# integrator.net
KiCad netlist of a schematic drawn in EAGLE
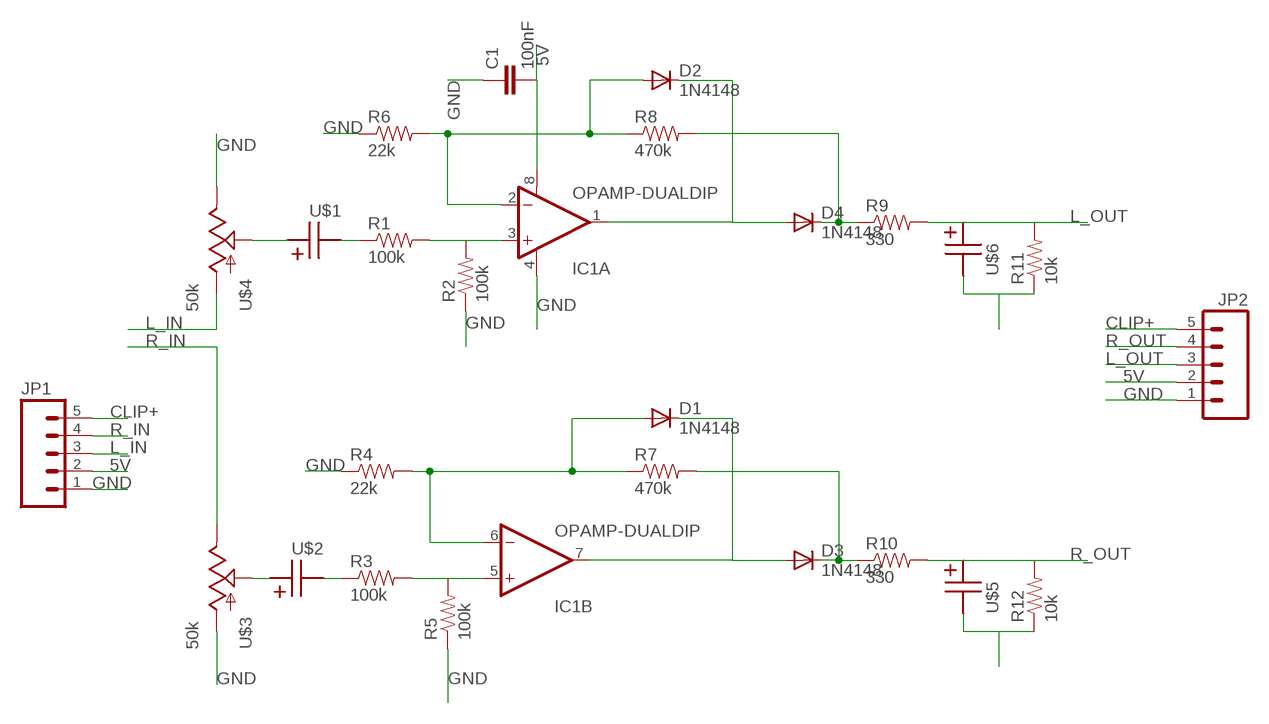
[diagram p0: schematic, sheet 1]

(export (version "E")
  (design (tool "Eeschema 10.0.6"))
  (components
    (comp (ref "C1")
      (value "100nF")
      (footprint "eagle-import:1206")
      (libsource (lib "eagle-import") (part "CAP1206"))
    )
    (comp (ref "D1")
      (value "1N4148")
      (footprint "eagle-import:DIODE-1N4148")
      (libsource (lib "eagle-import") (part "DIODE1N4148"))
    )
    (comp (ref "D2")
      (value "1N4148")
      (footprint "eagle-import:DIODE-1N4148")
      (libsource (lib "eagle-import") (part "DIODE1N4148"))
    )
    (comp (ref "D3")
      (value "1N4148")
      (footprint "eagle-import:DIODE-1N4148")
      (libsource (lib "eagle-import") (part "DIODE1N4148"))
    )
    (comp (ref "D4")
      (value "1N4148")
      (footprint "eagle-import:DIODE-1N4148")
      (libsource (lib "eagle-import") (part "DIODE1N4148"))
    )
    (comp (ref "IC1")
      (value "OPAMP-DUALDIP")
      (footprint "eagle-import:DIP08")
      (libsource (lib "eagle-import") (part "OPAMP-DUALDIP"))
    )
    (comp (ref "JP1")
      (value "M05SMD2")
      (footprint "eagle-import:1X05-1MM-RA")
      (libsource (lib "eagle-import") (part "M05SMD2"))
    )
    (comp (ref "JP2")
      (value "M05SMD2")
      (footprint "eagle-import:1X05-1MM-RA")
      (libsource (lib "eagle-import") (part "M05SMD2"))
    )
    (comp (ref "R1")
      (value "100k")
      (footprint "eagle-import:AXIAL-0.4")
      (libsource (lib "eagle-import") (part "RESISTORPTH-1/4W"))
    )
    (comp (ref "R2")
      (value "100k")
      (footprint "eagle-import:AXIAL-0.4")
      (libsource (lib "eagle-import") (part "RESISTORPTH-1/4W"))
    )
    (comp (ref "R3")
      (value "100k")
      (footprint "eagle-import:AXIAL-0.4")
      (libsource (lib "eagle-import") (part "RESISTORPTH-1/4W"))
    )
    (comp (ref "R4")
      (value "22k")
      (footprint "eagle-import:AXIAL-0.4")
      (libsource (lib "eagle-import") (part "RESISTORPTH-1/4W"))
    )
    (comp (ref "R5")
      (value "100k")
      (footprint "eagle-import:AXIAL-0.4")
      (libsource (lib "eagle-import") (part "RESISTORPTH-1/4W"))
    )
    (comp (ref "R6")
      (value "22k")
      (footprint "eagle-import:AXIAL-0.4")
      (libsource (lib "eagle-import") (part "RESISTORPTH-1/4W"))
    )
    (comp (ref "R7")
      (value "470k")
      (footprint "eagle-import:AXIAL-0.4")
      (libsource (lib "eagle-import") (part "RESISTORPTH-1/4W"))
    )
    (comp (ref "R8")
      (value "470k")
      (footprint "eagle-import:AXIAL-0.4")
      (libsource (lib "eagle-import") (part "RESISTORPTH-1/4W"))
    )
    (comp (ref "R9")
      (value "330")
      (footprint "eagle-import:AXIAL-0.4")
      (libsource (lib "eagle-import") (part "RESISTORPTH-1/4W"))
    )
    (comp (ref "R10")
      (value "330")
      (footprint "eagle-import:AXIAL-0.4")
      (libsource (lib "eagle-import") (part "RESISTORPTH-1/4W"))
    )
    (comp (ref "R11")
      (value "10k")
      (footprint "eagle-import:AXIAL-0.4")
      (libsource (lib "eagle-import") (part "RESISTORPTH-1/4W"))
    )
    (comp (ref "R12")
      (value "10k")
      (footprint "eagle-import:AXIAL-0.4")
      (libsource (lib "eagle-import") (part "RESISTORPTH-1/4W"))
    )
    (comp (ref "U$1")
      (value "6.8uF")
      (footprint "eagle-import:2MMLEAD_5MMDIAMETER")
      (libsource (lib "eagle-import") (part "5MM-12.5MM-POLAR2MMX5MM"))
    )
    (comp (ref "U$2")
      (value "6.8uF")
      (footprint "eagle-import:2MMLEAD_5MMDIAMETER")
      (libsource (lib "eagle-import") (part "5MM-12.5MM-POLAR2MMX5MM"))
    )
    (comp (ref "U$3")
      (value "50k")
      (footprint "eagle-import:ALPS_POT")
      (libsource (lib "eagle-import") (part "POT"))
    )
    (comp (ref "U$4")
      (value "50k")
      (footprint "eagle-import:ALPS_POT")
      (libsource (lib "eagle-import") (part "POT"))
    )
    (comp (ref "U$5")
      (value "2.2uF")
      (footprint "eagle-import:2MMLEAD_5MMDIAMETER")
      (libsource (lib "eagle-import") (part "5MM-12.5MM-POLAR2MMX5MM"))
    )
    (comp (ref "U$6")
      (value "2.2uF")
      (footprint "eagle-import:2MMLEAD_5MMDIAMETER")
      (libsource (lib "eagle-import") (part "5MM-12.5MM-POLAR2MMX5MM"))
    )
  )
  (nets
    (net (code "1") (name "/5V") (class "Default")
      (node (ref "C1") (pin "2") (pinfunction "2_2") (pintype "passive"))
      (node (ref "IC1") (pin "8") (pinfunction "V+_8") (pintype "power_in"))
      (node (ref "JP1") (pin "2") (pinfunction "2_2") (pintype "passive"))
      (node (ref "JP2") (pin "2") (pinfunction "2_2") (pintype "passive"))
    )
    (net (code "2") (name "/CLIP+") (class "Default")
      (node (ref "JP1") (pin "5") (pinfunction "5_5") (pintype "passive"))
      (node (ref "JP2") (pin "5") (pinfunction "5_5") (pintype "passive"))
    )
    (net (code "3") (name "/GND") (class "Default")
      (node (ref "C1") (pin "1") (pinfunction "1_1") (pintype "passive"))
      (node (ref "IC1") (pin "4") (pinfunction "V-_4") (pintype "power_in"))
      (node (ref "JP1") (pin "1") (pinfunction "1_1") (pintype "passive"))
      (node (ref "JP2") (pin "1") (pinfunction "1_1") (pintype "passive"))
      (node (ref "R11") (pin "P$1") (pinfunction "1_P$1") (pintype "passive"))
      (node (ref "R12") (pin "P$1") (pinfunction "1_P$1") (pintype "passive"))
      (node (ref "R2") (pin "P$1") (pinfunction "1_P$1") (pintype "passive"))
      (node (ref "R4") (pin "P$1") (pinfunction "1_P$1") (pintype "passive"))
      (node (ref "R5") (pin "P$1") (pinfunction "1_P$1") (pintype "passive"))
      (node (ref "R6") (pin "P$1") (pinfunction "1_P$1") (pintype "passive"))
      (node (ref "U$3") (pin "P$3") (pinfunction "A_P$3") (pintype "passive"))
      (node (ref "U$4") (pin "P$1") (pinfunction "E_P$1") (pintype "passive"))
      (node (ref "U$5") (pin "-") (pinfunction "-_-") (pintype "bidirectional"))
      (node (ref "U$6") (pin "-") (pinfunction "-_-") (pintype "bidirectional"))
    )
    (net (code "4") (name "/L_IN") (class "Default")
      (node (ref "JP1") (pin "3") (pinfunction "3_3") (pintype "passive"))
      (node (ref "U$4") (pin "P$3") (pinfunction "A_P$3") (pintype "passive"))
    )
    (net (code "5") (name "/L_OUT") (class "Default")
      (node (ref "JP2") (pin "3") (pinfunction "3_3") (pintype "passive"))
      (node (ref "R11") (pin "P$2") (pinfunction "2_P$2") (pintype "passive"))
      (node (ref "R9") (pin "P$2") (pinfunction "2_P$2") (pintype "passive"))
      (node (ref "U$6") (pin "+") (pinfunction "+_+") (pintype "bidirectional"))
    )
    (net (code "6") (name "/R_IN") (class "Default")
      (node (ref "JP1") (pin "4") (pinfunction "4_4") (pintype "passive"))
      (node (ref "U$3") (pin "P$1") (pinfunction "E_P$1") (pintype "passive"))
    )
    (net (code "7") (name "/R_OUT") (class "Default")
      (node (ref "JP2") (pin "4") (pinfunction "4_4") (pintype "passive"))
      (node (ref "R10") (pin "P$2") (pinfunction "2_P$2") (pintype "passive"))
      (node (ref "R12") (pin "P$2") (pinfunction "2_P$2") (pintype "passive"))
      (node (ref "U$5") (pin "+") (pinfunction "+_+") (pintype "bidirectional"))
    )
    (net (code "8") (name "Net-(IC1A-+IN)") (class "Default")
      (node (ref "IC1") (pin "3") (pinfunction "+IN_3") (pintype "input"))
      (node (ref "R1") (pin "P$2") (pinfunction "2_P$2") (pintype "passive"))
      (node (ref "R2") (pin "P$2") (pinfunction "2_P$2") (pintype "passive"))
    )
    (net (code "9") (name "Net-(IC1A--IN)") (class "Default")
      (node (ref "D2") (pin "A") (pinfunction "A_A") (pintype "passive"))
      (node (ref "IC1") (pin "2") (pinfunction "-IN_2") (pintype "input"))
      (node (ref "R6") (pin "P$2") (pinfunction "2_P$2") (pintype "passive"))
      (node (ref "R8") (pin "P$1") (pinfunction "1_P$1") (pintype "passive"))
    )
    (net (code "10") (name "Net-(IC1A-OUT)") (class "Default")
      (node (ref "D2") (pin "C") (pinfunction "C_C") (pintype "passive"))
      (node (ref "D4") (pin "A") (pinfunction "A_A") (pintype "passive"))
      (node (ref "IC1") (pin "1") (pinfunction "OUT_1") (pintype "output"))
    )
    (net (code "11") (name "Net-(IC1B-+IN)") (class "Default")
      (node (ref "IC1") (pin "5") (pinfunction "+IN_5") (pintype "input"))
      (node (ref "R3") (pin "P$2") (pinfunction "2_P$2") (pintype "passive"))
      (node (ref "R5") (pin "P$2") (pinfunction "2_P$2") (pintype "passive"))
    )
    (net (code "12") (name "Net-(IC1B--IN)") (class "Default")
      (node (ref "D1") (pin "A") (pinfunction "A_A") (pintype "passive"))
      (node (ref "IC1") (pin "6") (pinfunction "-IN_6") (pintype "input"))
      (node (ref "R4") (pin "P$2") (pinfunction "2_P$2") (pintype "passive"))
      (node (ref "R7") (pin "P$1") (pinfunction "1_P$1") (pintype "passive"))
    )
    (net (code "13") (name "Net-(IC1B-OUT)") (class "Default")
      (node (ref "D1") (pin "C") (pinfunction "C_C") (pintype "passive"))
      (node (ref "D3") (pin "A") (pinfunction "A_A") (pintype "passive"))
      (node (ref "IC1") (pin "7") (pinfunction "OUT_7") (pintype "output"))
    )
    (net (code "14") (name "Net-(R1-1)") (class "Default")
      (node (ref "R1") (pin "P$1") (pinfunction "1_P$1") (pintype "passive"))
      (node (ref "U$1") (pin "-") (pinfunction "-_-") (pintype "bidirectional"))
    )
    (net (code "15") (name "Net-(R3-1)") (class "Default")
      (node (ref "R3") (pin "P$1") (pinfunction "1_P$1") (pintype "passive"))
      (node (ref "U$2") (pin "-") (pinfunction "-_-") (pintype "bidirectional"))
    )
    (net (code "16") (name "Net-(R8-2)") (class "Default")
      (node (ref "D4") (pin "C") (pinfunction "C_C") (pintype "passive"))
      (node (ref "R8") (pin "P$2") (pinfunction "2_P$2") (pintype "passive"))
      (node (ref "R9") (pin "P$1") (pinfunction "1_P$1") (pintype "passive"))
    )
    (net (code "17") (name "Net-(R10-1)") (class "Default")
      (node (ref "D3") (pin "C") (pinfunction "C_C") (pintype "passive"))
      (node (ref "R10") (pin "P$1") (pinfunction "1_P$1") (pintype "passive"))
      (node (ref "R7") (pin "P$2") (pinfunction "2_P$2") (pintype "passive"))
    )
    (net (code "18") (name "Net-(U$3-S)") (class "Default")
      (node (ref "U$2") (pin "+") (pinfunction "+_+") (pintype "bidirectional"))
      (node (ref "U$3") (pin "P$2") (pinfunction "S_P$2") (pintype "passive"))
    )
    (net (code "19") (name "Net-(U$4-S)") (class "Default")
      (node (ref "U$1") (pin "+") (pinfunction "+_+") (pintype "bidirectional"))
      (node (ref "U$4") (pin "P$2") (pinfunction "S_P$2") (pintype "passive"))
    )
  )
)
